# DelSolClock.net
KiCad netlist of a schematic drawn in Altium Designer
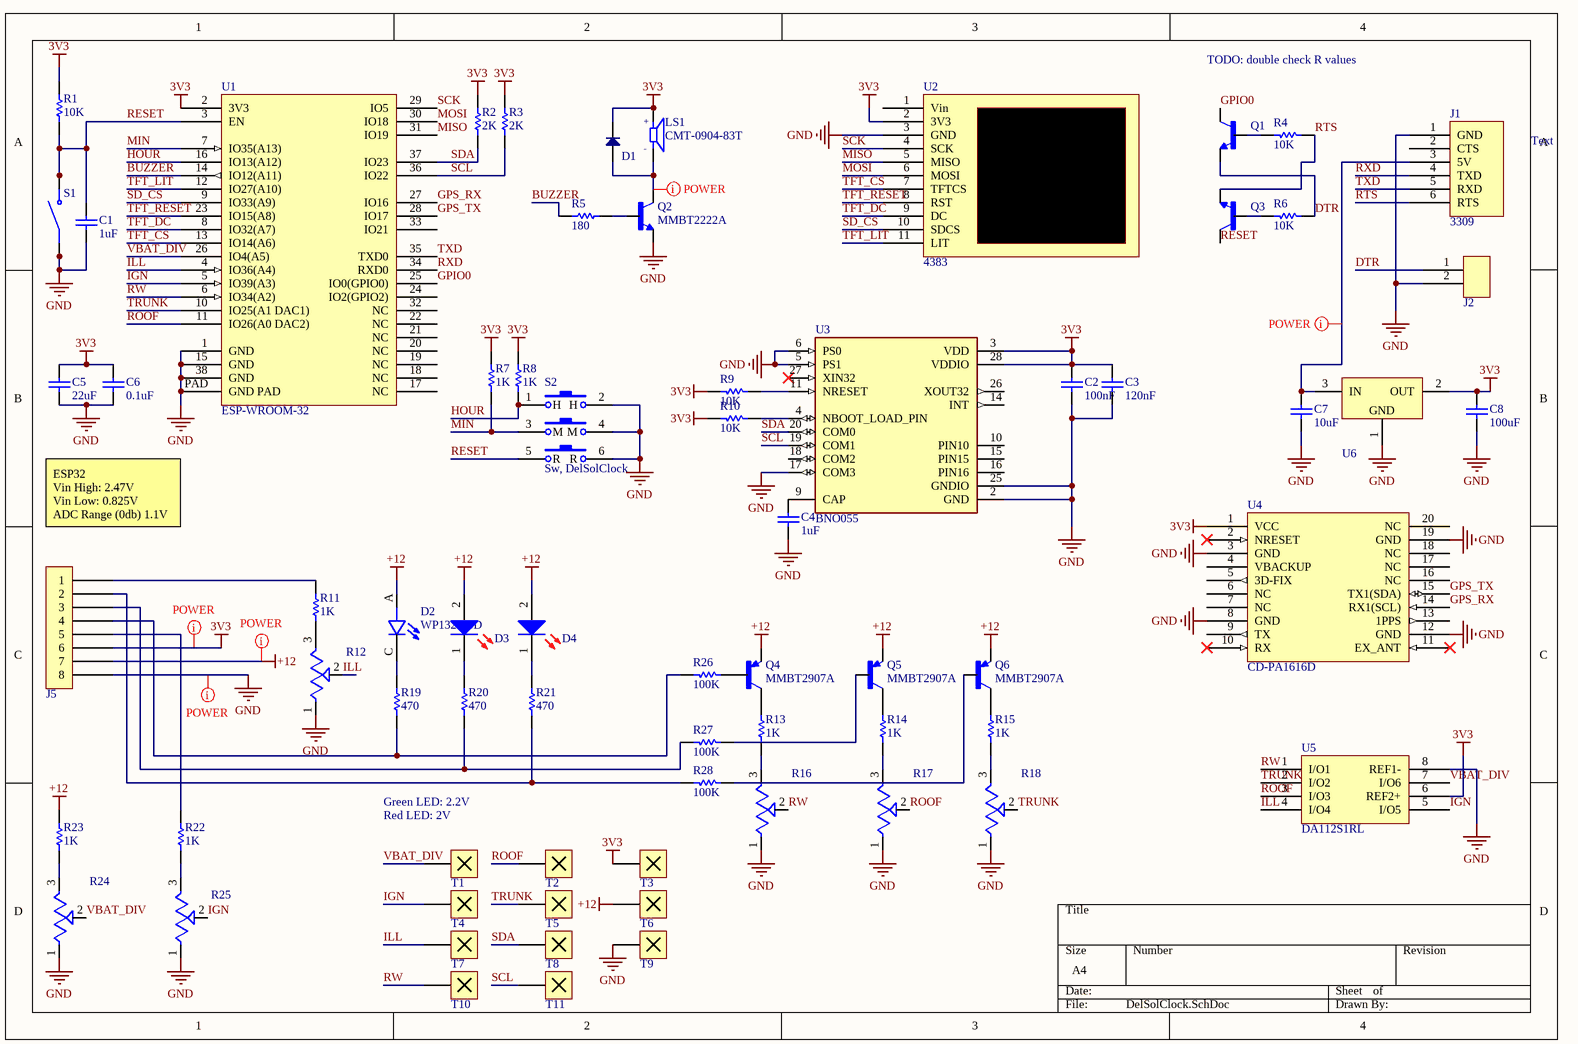
[diagram p0: DelSolClock.SchDoc]

(export (version "E")
  (design (tool "Eeschema 10.0.6"))
  (components
    (comp (ref "C1")
      (value "1uF")
      (footprint "0805 HD - Long")
      (description "Capacitor")
      (fields (field (name "Comment") "CL21B105KOFNNNG"))
      (libsource (lib "DiscreteComponents") (part "Cap"))
    )
    (comp (ref "C2")
      (value "100nF")
      (footprint "0805 HD - Long")
      (description "Capacitor")
      (fields (field (name "Comment") "CL21B104KBCNFNC"))
      (libsource (lib "DiscreteComponents") (part "Cap"))
    )
    (comp (ref "C3")
      (value "120nF")
      (footprint "0805 HD - Long")
      (description "Capacitor")
      (fields (field (name "Comment") "CC0805KRX7R9BB124"))
      (libsource (lib "DiscreteComponents") (part "Cap"))
    )
    (comp (ref "C4")
      (value "1uF")
      (footprint "0805 HD - Long")
      (description "Capacitor")
      (fields (field (name "Comment") "CL21B105KOFNNNG"))
      (libsource (lib "DiscreteComponents") (part "Cap"))
    )
    (comp (ref "C5")
      (value "22uF")
      (footprint "0805 HD - Long")
      (description "Capacitor")
      (fields (field (name "Comment") "Cap"))
      (libsource (lib "DiscreteComponents") (part "Cap"))
    )
    (comp (ref "C6")
      (value "0.1uF")
      (footprint "0805 HD - Long")
      (description "Capacitor")
      (fields (field (name "Comment") "Cap"))
      (libsource (lib "DiscreteComponents") (part "Cap"))
    )
    (comp (ref "C7")
      (value "10uF")
      (footprint "0805 HD - Long")
      (description "Capacitor")
      (fields (field (name "Comment") "Cap"))
      (libsource (lib "DiscreteComponents") (part "Cap"))
    )
    (comp (ref "C8")
      (value "100uF")
      (footprint "0805 HD - Long")
      (description "Capacitor")
      (fields (field (name "Comment") "Cap"))
      (libsource (lib "DiscreteComponents") (part "Cap"))
    )
    (comp (ref "D1")
      (value "SD0805S020S1R0")
      (footprint "0805 HD - Polarized")
      (description "Diode")
      (fields (field (name "MFG") "Panasonic - ECG"))
      (libsource (lib "DiscreteComponents") (part "Diode"))
    )
    (comp (ref "D2")
      (value "WP132XGD")
      (footprint "LEDRD254W50D405H1055")
      (description "Green 568nm LED Indication - Discrete 2.2V Radial")
      (fields (field (name "MF") "{'manufacturer': u'Kingbright'}"))
      (libsource (lib "SnapEDA_Library") (part "WP132XGD"))
    )
    (comp (ref "D3")
      (value "SSL-LX4673ID-LA20")
      (footprint "LED, SSL-LX4673ID-LA20")
      (description "LED, Red, 20mA, through hole, rectangular, 2V")
      (fields (field (name "MFG") "Lumex Opto/Components Inc."))
      (libsource (lib "DiscreteComponents") (part "LED, SSL-LX4673ID-LA20"))
    )
    (comp (ref "D4")
      (value "SSL-LX4673ID-LA20")
      (footprint "LED, SSL-LX4673ID-LA20")
      (description "LED, Red, 20mA, through hole, rectangular, 2V")
      (fields (field (name "MFG") "Lumex Opto/Components Inc."))
      (libsource (lib "DiscreteComponents") (part "LED, SSL-LX4673ID-LA20"))
    )
    (comp (ref "J1")
      (value "3309")
      (footprint "Conn, 3309")
      (description "Conn, Serial USB Adafruit CP2104 Friend")
      (fields (field (name "MFG") "Adafruit"))
      (libsource (lib "Connectors") (part "Conn, 3309"))
    )
    (comp (ref "J2")
      (value "90120-0122")
      (footprint "CONN, HEADER, 2x1 0.1 Pitch Unshrouded")
      (description "Header, 2x1 0.1\" Unshrouded Tin")
      (fields (field (name "MFG") "Molex Connector Corporation"))
      (libsource (lib "Connectors") (part "Conn, 90120-0122"))
    )
    (comp (ref "J5")
      (value "68000-408HLF")
      (footprint "Conn, Header, 8x1 0.1 Pitch Unshrouded")
      (description "Header, 8x1 0.1\" Unshrouded Tin")
      (fields (field (name "MFG") "FCI"))
      (libsource (lib "Connectors") (part "Conn, 68000-408HLF"))
    )
    (comp (ref "LS1")
      (value "CMT-0904-83T")
      (footprint "XDCR_CMT-0904-83T")
      (fields (field (name "MF") "{'manufacturer': u'CUI Devices'}"))
      (libsource (lib "SnapEDA_Library") (part "CMT-0904-83T"))
    )
    (comp (ref "Q1")
      (value "MMBT2222A")
      (footprint "SOT23")
      (description "<h3>2N2222 General Purpose NPN Transistor</h3>")
      (fields (field (name "MF") "{'manufacturer': u'ON Semiconductor'}"))
      (libsource (lib "SnapEDA_Library") (part "MMBT2222A"))
    )
    (comp (ref "Q2")
      (value "MMBT2222A")
      (footprint "SOT23")
      (description "<h3>2N2222 General Purpose NPN Transistor</h3>")
      (fields (field (name "MF") "{'manufacturer': u'ON Semiconductor'}"))
      (libsource (lib "") (part "MMBT2222A_2"))
    )
    (comp (ref "Q3")
      (value "MMBT2222A")
      (footprint "SOT23")
      (description "<h3>2N2222 General Purpose NPN Transistor</h3>")
      (fields (field (name "MF") "{'manufacturer': u'ON Semiconductor'}"))
      (libsource (lib "") (part "MMBT2222A_1"))
    )
    (comp (ref "Q4")
      (value "MMBT2907A")
      (footprint "TRANS_MMBT2907A")
      (description "350mW, PNP Small Signal Transistor")
      (fields (field (name "MF") "{'manufacturer': u'STMicroelectronics'}"))
      (libsource (lib "SnapEDA_Library") (part "MMBT2907A"))
    )
    (comp (ref "Q5")
      (value "MMBT2907A")
      (footprint "TRANS_MMBT2907A")
      (description "350mW, PNP Small Signal Transistor")
      (fields (field (name "MF") "{'manufacturer': u'STMicroelectronics'}"))
      (libsource (lib "SnapEDA_Library") (part "MMBT2907A"))
    )
    (comp (ref "Q6")
      (value "MMBT2907A")
      (footprint "TRANS_MMBT2907A")
      (description "350mW, PNP Small Signal Transistor")
      (fields (field (name "MF") "{'manufacturer': u'STMicroelectronics'}"))
      (libsource (lib "SnapEDA_Library") (part "MMBT2907A"))
    )
    (comp (ref "R1")
      (value "10K")
      (footprint "0805 HD - Long")
      (description "Resistor")
      (fields (field (name "Comment") "RNCP0805FTD10K0"))
      (libsource (lib "DiscreteComponents") (part "Res"))
    )
    (comp (ref "R2")
      (value "2K")
      (footprint "0805 HD - Long")
      (description "Resistor")
      (fields (field (name "Comment") "AC0805FR-7W2KL"))
      (libsource (lib "DiscreteComponents") (part "Res"))
    )
    (comp (ref "R3")
      (value "2K")
      (footprint "0805 HD - Long")
      (description "Resistor")
      (fields (field (name "Comment") "AC0805FR-7W2KL"))
      (libsource (lib "DiscreteComponents") (part "Res"))
    )
    (comp (ref "R4")
      (value "10K")
      (footprint "0805 HD - Long")
      (description "Resistor")
      (fields (field (name "Comment") "RNCP0805FTD10K0"))
      (libsource (lib "DiscreteComponents") (part "Res"))
    )
    (comp (ref "R5")
      (value "180")
      (footprint "0805 HD - Long")
      (description "Resistor")
      (fields (field (name "Comment") "ESR10EZPJ181"))
      (libsource (lib "DiscreteComponents") (part "Res"))
    )
    (comp (ref "R6")
      (value "10K")
      (footprint "0805 HD - Long")
      (description "Resistor")
      (fields (field (name "Comment") "RNCP0805FTD10K0"))
      (libsource (lib "DiscreteComponents") (part "Res"))
    )
    (comp (ref "R7")
      (value "1K")
      (footprint "0805 HD - Long")
      (description "Resistor")
      (fields (field (name "Comment") "CRGH0805J1K0"))
      (libsource (lib "DiscreteComponents") (part "Res"))
    )
    (comp (ref "R8")
      (value "1K")
      (footprint "0805 HD - Long")
      (description "Resistor")
      (fields (field (name "Comment") "CRGH0805J1K0"))
      (libsource (lib "DiscreteComponents") (part "Res"))
    )
    (comp (ref "R9")
      (value "10K")
      (footprint "0805 HD - Long")
      (description "Resistor")
      (fields (field (name "Comment") "RNCP0805FTD10K0"))
      (libsource (lib "DiscreteComponents") (part "Res"))
    )
    (comp (ref "R10")
      (value "10K")
      (footprint "0805 HD - Long")
      (description "Resistor")
      (fields (field (name "Comment") "RNCP0805FTD10K0"))
      (libsource (lib "DiscreteComponents") (part "Res"))
    )
    (comp (ref "R11")
      (value "1K")
      (footprint "0805 HD - Long")
      (description "Resistor")
      (fields (field (name "Comment") "CRGH0805J1K0"))
      (libsource (lib "DiscreteComponents") (part "Res"))
    )
    (comp (ref "R12")
      (value "PVG3G104C01R00")
      (footprint "TRIM_PVG3G104C01R00")
      (description "100 kOhms 0.25W, 1/4W Gull Wing Surface Mount Trimmer Potentiometer Cermet 1 Turn Top Adjustment")
      (fields (field (name "MF") "{'manufacturer': u'Bourns'}"))
      (libsource (lib "SnapEDA_Library") (part "PVG3G104C01R00"))
    )
    (comp (ref "R13")
      (value "1K")
      (footprint "0805 HD - Long")
      (description "Resistor")
      (fields (field (name "Comment") "CRGH0805J1K0"))
      (libsource (lib "DiscreteComponents") (part "Res"))
    )
    (comp (ref "R14")
      (value "1K")
      (footprint "0805 HD - Long")
      (description "Resistor")
      (fields (field (name "Comment") "CRGH0805J1K0"))
      (libsource (lib "DiscreteComponents") (part "Res"))
    )
    (comp (ref "R15")
      (value "1K")
      (footprint "0805 HD - Long")
      (description "Resistor")
      (fields (field (name "Comment") "CRGH0805J1K0"))
      (libsource (lib "DiscreteComponents") (part "Res"))
    )
    (comp (ref "R16")
      (value "PVG3G104C01R00")
      (footprint "TRIM_PVG3G104C01R00")
      (description "10 kOhms 0.25W, 1/4W Gull Wing Surface Mount Trimmer Potentiometer Cermet 1 Turn Top Adjustment")
      (fields (field (name "MF") "{'manufacturer': u'Bourns'}"))
      (libsource (lib "SnapEDA_Library") (part "PVG3G104C01R00"))
    )
    (comp (ref "R17")
      (value "PVG3G104C01R00")
      (footprint "TRIM_PVG3G104C01R00")
      (description "10 kOhms 0.25W, 1/4W Gull Wing Surface Mount Trimmer Potentiometer Cermet 1 Turn Top Adjustment")
      (fields (field (name "MF") "{'manufacturer': u'Bourns'}"))
      (libsource (lib "SnapEDA_Library") (part "PVG3G104C01R00"))
    )
    (comp (ref "R18")
      (value "PVG3G104C01R00")
      (footprint "TRIM_PVG3G104C01R00")
      (description "10 kOhms 0.25W, 1/4W Gull Wing Surface Mount Trimmer Potentiometer Cermet 1 Turn Top Adjustment")
      (fields (field (name "MF") "{'manufacturer': u'Bourns'}"))
      (libsource (lib "SnapEDA_Library") (part "PVG3G104C01R00"))
    )
    (comp (ref "R19")
      (value "470")
      (footprint "0805 HD - Long")
      (description "Resistor")
      (fields (field (name "Comment") "ESR10EZPJ471"))
      (libsource (lib "DiscreteComponents") (part "Res"))
    )
    (comp (ref "R20")
      (value "470")
      (footprint "0805 HD - Long")
      (description "Resistor")
      (fields (field (name "Comment") "ESR10EZPJ471"))
      (libsource (lib "DiscreteComponents") (part "Res"))
    )
    (comp (ref "R21")
      (value "470")
      (footprint "0805 HD - Long")
      (description "Resistor")
      (fields (field (name "Comment") "ESR10EZPJ471"))
      (libsource (lib "DiscreteComponents") (part "Res"))
    )
    (comp (ref "R22")
      (value "1K")
      (footprint "0805 HD - Long")
      (description "Resistor")
      (fields (field (name "Comment") "CRGH0805J1K0"))
      (libsource (lib "DiscreteComponents") (part "Res"))
    )
    (comp (ref "R23")
      (value "1K")
      (footprint "0805 HD - Long")
      (description "Resistor")
      (fields (field (name "Comment") "CRGH0805J1K0"))
      (libsource (lib "DiscreteComponents") (part "Res"))
    )
    (comp (ref "R24")
      (value "PVG3G104C01R00")
      (footprint "TRIM_PVG3G104C01R00")
      (description "100 kOhms 0.25W, 1/4W Gull Wing Surface Mount Trimmer Potentiometer Cermet 1 Turn Top Adjustment")
      (fields (field (name "MF") "{'manufacturer': u'Bourns'}"))
      (libsource (lib "SnapEDA_Library") (part "PVG3G104C01R00"))
    )
    (comp (ref "R25")
      (value "PVG3G104C01R00")
      (footprint "TRIM_PVG3G104C01R00")
      (description "100 kOhms 0.25W, 1/4W Gull Wing Surface Mount Trimmer Potentiometer Cermet 1 Turn Top Adjustment")
      (fields (field (name "MF") "{'manufacturer': u'Bourns'}"))
      (libsource (lib "SnapEDA_Library") (part "PVG3G104C01R00"))
    )
    (comp (ref "R26")
      (value "100K")
      (footprint "0805 HD - Long")
      (description "Resistor")
      (fields (field (name "Comment") "CRGH0805J100K"))
      (libsource (lib "DiscreteComponents") (part "Res"))
    )
    (comp (ref "R27")
      (value "100K")
      (footprint "0805 HD - Long")
      (description "Resistor")
      (fields (field (name "Comment") "CRGH0805J100K"))
      (libsource (lib "DiscreteComponents") (part "Res"))
    )
    (comp (ref "R28")
      (value "100K")
      (footprint "0805 HD - Long")
      (description "Resistor")
      (fields (field (name "Comment") "CRGH0805J100K"))
      (libsource (lib "DiscreteComponents") (part "Res"))
    )
    (comp (ref "S1")
      (value "8-1437565-0")
      (footprint "SW_8-1437565-0")
      (fields (field (name "MF") "{'manufacturer': u'TE Connectivity'}"))
      (libsource (lib "SnapEDA_Library") (part "8-1437565-0"))
    )
    (comp (ref "S2")
      (value "Sw, DelSolClock")
      (footprint "Sw, DelSolClock")
      (description "Switch, Del Sol Clock, elastomeric")
      (libsource (lib "Connectors") (part "Sw, DelSolClock"))
    )
    (comp (ref "T1")
      (value "Test Point")
      (footprint "5002 Test Point")
      (fields (field (name "MFG") "Keystone Electronics"))
      (libsource (lib "Connectors") (part "Test Point"))
    )
    (comp (ref "T2")
      (value "Test Point")
      (footprint "5002 Test Point")
      (fields (field (name "MFG") "Keystone Electronics"))
      (libsource (lib "Connectors") (part "Test Point"))
    )
    (comp (ref "T3")
      (value "Test Point")
      (footprint "5002 Test Point")
      (fields (field (name "MFG") "Keystone Electronics"))
      (libsource (lib "Connectors") (part "Test Point"))
    )
    (comp (ref "T4")
      (value "Test Point")
      (footprint "5002 Test Point")
      (fields (field (name "MFG") "Keystone Electronics"))
      (libsource (lib "Connectors") (part "Test Point"))
    )
    (comp (ref "T5")
      (value "Test Point")
      (footprint "5002 Test Point")
      (fields (field (name "MFG") "Keystone Electronics"))
      (libsource (lib "Connectors") (part "Test Point"))
    )
    (comp (ref "T6")
      (value "Test Point")
      (footprint "5002 Test Point")
      (fields (field (name "MFG") "Keystone Electronics"))
      (libsource (lib "Connectors") (part "Test Point"))
    )
    (comp (ref "T7")
      (value "Test Point")
      (footprint "5002 Test Point")
      (fields (field (name "MFG") "Keystone Electronics"))
      (libsource (lib "Connectors") (part "Test Point"))
    )
    (comp (ref "T8")
      (value "Test Point")
      (footprint "5002 Test Point")
      (fields (field (name "MFG") "Keystone Electronics"))
      (libsource (lib "Connectors") (part "Test Point"))
    )
    (comp (ref "T9")
      (value "Test Point")
      (footprint "5002 Test Point")
      (fields (field (name "MFG") "Keystone Electronics"))
      (libsource (lib "Connectors") (part "Test Point"))
    )
    (comp (ref "T10")
      (value "Test Point")
      (footprint "5002 Test Point")
      (fields (field (name "MFG") "Keystone Electronics"))
      (libsource (lib "Connectors") (part "Test Point"))
    )
    (comp (ref "T11")
      (value "Test Point")
      (footprint "5002 Test Point")
      (fields (field (name "MFG") "Keystone Electronics"))
      (libsource (lib "Connectors") (part "Test Point"))
    )
    (comp (ref "U1")
      (value "ESP-WROOM-32")
      (footprint "MODULE, ESP32-WROOM-32")
      (description "Module, Wifi Module, ESP32 4MB Flash 520K RAM")
      (fields (field (name "MFG") "Espressif"))
      (libsource (lib "Modules") (part "Module, ESP-WROOM-32"))
    )
    (comp (ref "U2")
      (value "4383")
      (footprint "Module, Adafruit TFT")
      (description "Module, Display, Graphic TFT 240x135 Color, ST7789")
      (fields (field (name "MFG") "Adafruit"))
      (libsource (lib "Modules") (part "Module, Adafruit TFT"))
    )
    (comp (ref "U3")
      (value "BNO055")
      (footprint "LGA28R50P4X10_380X520X100")
      (description "BNO055 9-axis Absolute Orientation Sensor ( SiP ) w/Sensors and Sensor Fusion")
      (fields (field (name "MF") "{'manufacturer': u'Bosch'}"))
      (libsource (lib "SnapEDA_Library") (part "BNO055"))
    )
    (comp (ref "U4")
      (value "CD-PA1616D")
      (footprint "Module, CD-PA1616D")
      (description "Module, GPS, module with integrated antenna")
      (fields (field (name "MFG") "CD Technology"))
      (libsource (lib "Modules") (part "Module, CD-PA1616D"))
    )
    (comp (ref "U5")
      (value "DA112S1RL")
      (footprint "IC, DA112S1RL")
      (description "IC, TVS Diode, 6 channel")
      (libsource (lib "IntegratedCircuits") (part "IC, DA112S1RL"))
    )
    (comp (ref "U6")
      (value "TLV1117-33CDCYR")
      (footprint "SOT230P700X180-4N Regulator 3.3V 800mA")
      (description "IC, Regulator 3.3V 800mA LDO 15V max SOT-223")
      (fields (field (name "MFG") "Texas Instruments"))
      (libsource (lib "IntegratedCircuits") (part "IC, TLV1117-33CDCYR"))
    )
  )
  (nets
    (net (code "1") (name "+12") (class "Default")
      (node (ref "D2") (pin "A") (pinfunction "A_A") (pintype "passive"))
      (node (ref "D3") (pin "2") (pinfunction "A_2") (pintype "passive"))
      (node (ref "D4") (pin "2") (pinfunction "A_2") (pintype "passive"))
      (node (ref "J5") (pin "7") (pinfunction "7_7") (pintype "passive"))
      (node (ref "Q4") (pin "2") (pinfunction "E_2") (pintype "passive"))
      (node (ref "Q5") (pin "2") (pinfunction "E_2") (pintype "passive"))
      (node (ref "Q6") (pin "2") (pinfunction "E_2") (pintype "passive"))
      (node (ref "R23") (pin "1") (pinfunction "1_1") (pintype "passive"))
      (node (ref "T6") (pin "1") (pinfunction "1_1") (pintype "passive"))
    )
    (net (code "2") (name "/BUZZER") (class "Default")
      (node (ref "R5") (pin "1") (pinfunction "1_1") (pintype "passive"))
      (node (ref "U1") (pin "14") (pinfunction "IO12(A11)_14") (pintype "output"))
    )
    (net (code "3") (name "/DTR") (class "Default")
      (node (ref "J2") (pin "1") (pintype "passive"))
      (node (ref "Q1") (pin "2") (pinfunction "E_2") (pintype "passive"))
      (node (ref "R6") (pin "2") (pinfunction "2_2") (pintype "passive"))
    )
    (net (code "4") (name "/GPIO0") (class "Default")
      (node (ref "Q1") (pin "3") (pinfunction "C_3") (pintype "passive"))
      (node (ref "U1") (pin "25") (pinfunction "IO0(GPIO0)_25") (pintype "passive"))
    )
    (net (code "5") (name "/GPS_RX") (class "Default")
      (node (ref "U1") (pin "27") (pinfunction "IO16_27") (pintype "passive"))
      (node (ref "U4") (pin "14") (pinfunction "RX1(SCL)_14") (pintype "input"))
    )
    (net (code "6") (name "/GPS_TX") (class "Default")
      (node (ref "U1") (pin "28") (pinfunction "IO17_28") (pintype "passive"))
      (node (ref "U4") (pin "15") (pinfunction "TX1(SDA)_15") (pintype "bidirectional"))
    )
    (net (code "7") (name "/HOUR") (class "Default")
      (node (ref "R8") (pin "1") (pinfunction "1_1") (pintype "passive"))
      (node (ref "S2") (pin "1") (pinfunction "H_1") (pintype "passive"))
      (node (ref "U1") (pin "16") (pinfunction "IO13(A12)_16") (pintype "passive"))
    )
    (net (code "8") (name "/IGN") (class "Default")
      (node (ref "R25") (pin "2") (pinfunction "WIPER_2") (pintype "passive"))
      (node (ref "T4") (pin "1") (pinfunction "1_1") (pintype "passive"))
      (node (ref "U1") (pin "5") (pinfunction "IO39(A3)_5") (pintype "input"))
      (node (ref "U5") (pin "5") (pinfunction "I/O5_5") (pintype "passive"))
    )
    (net (code "9") (name "/ILL") (class "Default")
      (node (ref "R12") (pin "2") (pinfunction "WIPER_2") (pintype "passive"))
      (node (ref "T7") (pin "1") (pinfunction "1_1") (pintype "passive"))
      (node (ref "U1") (pin "4") (pinfunction "IO36(A4)_4") (pintype "input"))
      (node (ref "U5") (pin "4") (pinfunction "I/O4_4") (pintype "passive"))
    )
    (net (code "10") (name "/MIN") (class "Default")
      (node (ref "R7") (pin "1") (pinfunction "1_1") (pintype "passive"))
      (node (ref "S2") (pin "3") (pinfunction "M_3") (pintype "passive"))
      (node (ref "U1") (pin "7") (pinfunction "IO35(A13)_7") (pintype "input"))
    )
    (net (code "11") (name "/MISO") (class "Default")
      (node (ref "U1") (pin "31") (pinfunction "IO19_31") (pintype "passive"))
      (node (ref "U2") (pin "5") (pinfunction "MISO_5") (pintype "passive"))
    )
    (net (code "12") (name "/MOSI") (class "Default")
      (node (ref "U1") (pin "30") (pinfunction "IO18_30") (pintype "passive"))
      (node (ref "U2") (pin "6") (pinfunction "MOSI_6") (pintype "passive"))
    )
    (net (code "13") (name "/RESET") (class "Default")
      (node (ref "C1") (pin "2") (pinfunction "2_2") (pintype "passive"))
      (node (ref "Q3") (pin "3") (pinfunction "C_3") (pintype "passive"))
      (node (ref "R1") (pin "1") (pinfunction "1_1") (pintype "passive"))
      (node (ref "S1") (pin "3") (pinfunction "NO_3") (pintype "passive"))
      (node (ref "S1") (pin "4") (pinfunction "NO_4") (pintype "passive"))
      (node (ref "S2") (pin "5") (pinfunction "R_5") (pintype "passive"))
      (node (ref "U1") (pin "3") (pinfunction "EN_3") (pintype "passive"))
    )
    (net (code "14") (name "/ROOF") (class "Default")
      (node (ref "R17") (pin "2") (pinfunction "WIPER_2") (pintype "passive"))
      (node (ref "T2") (pin "1") (pinfunction "1_1") (pintype "passive"))
      (node (ref "U1") (pin "11") (pinfunction "IO26(A0_DAC2)_11") (pintype "passive"))
      (node (ref "U5") (pin "3") (pinfunction "I/O3_3") (pintype "passive"))
    )
    (net (code "15") (name "/RTS") (class "Default")
      (node (ref "J1") (pin "6") (pinfunction "RTS_6") (pintype "passive"))
      (node (ref "Q3") (pin "2") (pinfunction "E_2") (pintype "passive"))
      (node (ref "R4") (pin "2") (pinfunction "2_2") (pintype "passive"))
    )
    (net (code "16") (name "/RW") (class "Default")
      (node (ref "R16") (pin "2") (pinfunction "WIPER_2") (pintype "passive"))
      (node (ref "T10") (pin "1") (pinfunction "1_1") (pintype "passive"))
      (node (ref "U1") (pin "6") (pinfunction "IO34(A2)_6") (pintype "input"))
      (node (ref "U5") (pin "1") (pinfunction "I/O1_1") (pintype "passive"))
    )
    (net (code "17") (name "/RXD") (class "Default")
      (node (ref "J1") (pin "4") (pinfunction "TXD_4") (pintype "passive"))
      (node (ref "U1") (pin "34") (pinfunction "RXD0_34") (pintype "passive"))
    )
    (net (code "18") (name "/SCK") (class "Default")
      (node (ref "U1") (pin "29") (pinfunction "IO5_29") (pintype "passive"))
      (node (ref "U2") (pin "4") (pinfunction "SCK_4") (pintype "passive"))
    )
    (net (code "19") (name "/SCL") (class "Default")
      (node (ref "R3") (pin "1") (pinfunction "1_1") (pintype "passive"))
      (node (ref "T11") (pin "1") (pinfunction "1_1") (pintype "passive"))
      (node (ref "U1") (pin "36") (pinfunction "IO22_36") (pintype "passive"))
      (node (ref "U3") (pin "19") (pinfunction "COM1_19") (pintype "bidirectional"))
    )
    (net (code "20") (name "/SDA") (class "Default")
      (node (ref "R2") (pin "1") (pinfunction "1_1") (pintype "passive"))
      (node (ref "T8") (pin "1") (pinfunction "1_1") (pintype "passive"))
      (node (ref "U1") (pin "37") (pinfunction "IO23_37") (pintype "passive"))
      (node (ref "U3") (pin "20") (pinfunction "COM0_20") (pintype "bidirectional"))
    )
    (net (code "21") (name "/SD_CS") (class "Default")
      (node (ref "U1") (pin "9") (pinfunction "IO33(A9)_9") (pintype "passive"))
      (node (ref "U2") (pin "10") (pinfunction "SDCS_10") (pintype "passive"))
    )
    (net (code "22") (name "/TFT_CS") (class "Default")
      (node (ref "U1") (pin "13") (pinfunction "IO14(A6)_13") (pintype "passive"))
      (node (ref "U2") (pin "7") (pinfunction "TFTCS_7") (pintype "passive"))
    )
    (net (code "23") (name "/TFT_DC") (class "Default")
      (node (ref "U1") (pin "8") (pinfunction "IO32(A7)_8") (pintype "passive"))
      (node (ref "U2") (pin "9") (pinfunction "DC_9") (pintype "passive"))
    )
    (net (code "24") (name "/TFT_LIT") (class "Default")
      (node (ref "U1") (pin "12") (pinfunction "IO27(A10)_12") (pintype "passive"))
      (node (ref "U2") (pin "11") (pinfunction "LIT_11") (pintype "passive"))
    )
    (net (code "25") (name "/TFT_RESET") (class "Default")
      (node (ref "U1") (pin "23") (pinfunction "IO15(A8)_23") (pintype "passive"))
      (node (ref "U2") (pin "8") (pinfunction "RST_8") (pintype "passive"))
    )
    (net (code "26") (name "/TRUNK") (class "Default")
      (node (ref "R18") (pin "2") (pinfunction "WIPER_2") (pintype "passive"))
      (node (ref "T5") (pin "1") (pinfunction "1_1") (pintype "passive"))
      (node (ref "U1") (pin "10") (pinfunction "IO25(A1_DAC1)_10") (pintype "passive"))
      (node (ref "U5") (pin "2") (pinfunction "I/O2_2") (pintype "passive"))
    )
    (net (code "27") (name "/TXD") (class "Default")
      (node (ref "J1") (pin "5") (pinfunction "RXD_5") (pintype "passive"))
      (node (ref "U1") (pin "35") (pinfunction "TXD0_35") (pintype "passive"))
    )
    (net (code "28") (name "/VBAT_DIV") (class "Default")
      (node (ref "R24") (pin "2") (pinfunction "WIPER_2") (pintype "passive"))
      (node (ref "T1") (pin "1") (pinfunction "1_1") (pintype "passive"))
      (node (ref "U1") (pin "26") (pinfunction "IO4(A5)_26") (pintype "passive"))
      (node (ref "U5") (pin "7") (pinfunction "I/O6_7") (pintype "passive"))
    )
    (net (code "29") (name "3V3") (class "Default")
      (node (ref "C2") (pin "1") (pinfunction "1_1") (pintype "passive"))
      (node (ref "C3") (pin "1") (pinfunction "1_1") (pintype "passive"))
      (node (ref "C5") (pin "2") (pinfunction "2_2") (pintype "passive"))
      (node (ref "C6") (pin "2") (pinfunction "2_2") (pintype "passive"))
      (node (ref "C8") (pin "2") (pinfunction "2_2") (pintype "passive"))
      (node (ref "D1") (pin "1") (pinfunction "C_1") (pintype "passive"))
      (node (ref "J5") (pin "6") (pinfunction "6_6") (pintype "passive"))
      (node (ref "LS1") (pin "P") (pinfunction "P_P") (pintype "passive"))
      (node (ref "R1") (pin "2") (pinfunction "2_2") (pintype "passive"))
      (node (ref "R10") (pin "1") (pinfunction "1_1") (pintype "passive"))
      (node (ref "R2") (pin "2") (pinfunction "2_2") (pintype "passive"))
      (node (ref "R3") (pin "2") (pinfunction "2_2") (pintype "passive"))
      (node (ref "R7") (pin "2") (pinfunction "2_2") (pintype "passive"))
      (node (ref "R8") (pin "2") (pinfunction "2_2") (pintype "passive"))
      (node (ref "R9") (pin "1") (pinfunction "1_1") (pintype "passive"))
      (node (ref "T3") (pin "1") (pinfunction "1_1") (pintype "passive"))
      (node (ref "U1") (pin "2") (pinfunction "3V3_2") (pintype "passive"))
      (node (ref "U2") (pin "2") (pinfunction "3V3_2") (pintype "passive"))
      (node (ref "U3") (pin "28") (pinfunction "VDDIO_28") (pintype "power_in"))
      (node (ref "U3") (pin "3") (pinfunction "VDD_3") (pintype "power_in"))
      (node (ref "U4") (pin "1") (pinfunction "VCC_1") (pintype "power_in"))
      (node (ref "U5") (pin "6") (pinfunction "REF2+_6") (pintype "passive"))
      (node (ref "U6") (pin "2") (pinfunction "OUT_2") (pintype "passive"))
    )
    (net (code "30") (name "GND") (class "Default")
      (node (ref "C1") (pin "1") (pinfunction "1_1") (pintype "passive"))
      (node (ref "C2") (pin "2") (pinfunction "2_2") (pintype "passive"))
      (node (ref "C3") (pin "2") (pinfunction "2_2") (pintype "passive"))
      (node (ref "C4") (pin "1") (pinfunction "1_1") (pintype "passive"))
      (node (ref "C5") (pin "1") (pinfunction "1_1") (pintype "passive"))
      (node (ref "C6") (pin "1") (pinfunction "1_1") (pintype "passive"))
      (node (ref "C7") (pin "1") (pinfunction "1_1") (pintype "passive"))
      (node (ref "C8") (pin "1") (pinfunction "1_1") (pintype "passive"))
      (node (ref "J1") (pin "1") (pinfunction "GND_1") (pintype "passive"))
      (node (ref "J2") (pin "2") (pintype "passive"))
      (node (ref "J5") (pin "8") (pinfunction "8_8") (pintype "passive"))
      (node (ref "Q2") (pin "2") (pinfunction "E_2") (pintype "passive"))
      (node (ref "R12") (pin "1") (pinfunction "CCW_1") (pintype "passive"))
      (node (ref "R16") (pin "1") (pinfunction "CCW_1") (pintype "passive"))
      (node (ref "R17") (pin "1") (pinfunction "CCW_1") (pintype "passive"))
      (node (ref "R18") (pin "1") (pinfunction "CCW_1") (pintype "passive"))
      (node (ref "R24") (pin "1") (pinfunction "CCW_1") (pintype "passive"))
      (node (ref "R25") (pin "1") (pinfunction "CCW_1") (pintype "passive"))
      (node (ref "S1") (pin "1") (pinfunction "COM_1") (pintype "passive"))
      (node (ref "S1") (pin "2") (pinfunction "COM_2") (pintype "passive"))
      (node (ref "S2") (pin "2") (pinfunction "H_2") (pintype "passive"))
      (node (ref "S2") (pin "4") (pinfunction "M_4") (pintype "passive"))
      (node (ref "S2") (pin "6") (pinfunction "R_6") (pintype "passive"))
      (node (ref "T9") (pin "1") (pinfunction "1_1") (pintype "passive"))
      (node (ref "U1") (pin "1") (pinfunction "GND_1") (pintype "passive"))
      (node (ref "U1") (pin "15") (pinfunction "GND_15") (pintype "passive"))
      (node (ref "U1") (pin "38") (pinfunction "GND_38") (pintype "passive"))
      (node (ref "U1") (pin "PAD") (pinfunction "GND_PAD_PAD") (pintype "passive"))
      (node (ref "U2") (pin "3") (pinfunction "GND_3") (pintype "passive"))
      (node (ref "U3") (pin "17") (pinfunction "COM3_17") (pintype "bidirectional"))
      (node (ref "U3") (pin "2") (pinfunction "GND_2") (pintype "power_in"))
      (node (ref "U3") (pin "25") (pinfunction "GNDIO_25") (pintype "power_in"))
      (node (ref "U3") (pin "5") (pinfunction "PS1_5") (pintype "input"))
      (node (ref "U3") (pin "6") (pinfunction "PS0_6") (pintype "input"))
      (node (ref "U4") (pin "12") (pinfunction "GND_12") (pintype "power_in"))
      (node (ref "U4") (pin "19") (pinfunction "GND_19") (pintype "power_in"))
      (node (ref "U4") (pin "3") (pinfunction "GND_3") (pintype "power_in"))
      (node (ref "U4") (pin "8") (pinfunction "GND_8") (pintype "power_in"))
      (node (ref "U5") (pin "8") (pinfunction "REF1-_8") (pintype "passive"))
      (node (ref "U6") (pin "1") (pinfunction "GND_1") (pintype "passive"))
    )
    (net (code "31") (name "Net-(D1-A)") (class "Default")
      (node (ref "D1") (pin "2") (pinfunction "A_2") (pintype "passive"))
      (node (ref "LS1") (pin "N") (pinfunction "N_N") (pintype "passive"))
      (node (ref "Q2") (pin "3") (pinfunction "C_3") (pintype "passive"))
    )
    (net (code "32") (name "Net-(D2-PadC)") (class "Default")
      (node (ref "D2") (pin "C") (pinfunction "C_C") (pintype "passive"))
      (node (ref "R19") (pin "2") (pinfunction "2_2") (pintype "passive"))
    )
    (net (code "33") (name "Net-(D3-K)") (class "Default")
      (node (ref "D3") (pin "1") (pinfunction "K_1") (pintype "passive"))
      (node (ref "R20") (pin "2") (pinfunction "2_2") (pintype "passive"))
    )
    (net (code "34") (name "Net-(D4-K)") (class "Default")
      (node (ref "D4") (pin "1") (pinfunction "K_1") (pintype "passive"))
      (node (ref "R21") (pin "2") (pinfunction "2_2") (pintype "passive"))
    )
    (net (code "35") (name "Net-(J1-5V)") (class "Default")
      (node (ref "C7") (pin "2") (pinfunction "2_2") (pintype "passive"))
      (node (ref "J1") (pin "3") (pinfunction "5V_3") (pintype "passive"))
      (node (ref "U6") (pin "3") (pinfunction "IN_3") (pintype "passive"))
    )
    (net (code "36") (name "Net-(J5-Pad1)") (class "Default")
      (node (ref "J5") (pin "1") (pinfunction "1_1") (pintype "passive"))
      (node (ref "R11") (pin "2") (pinfunction "2_2") (pintype "passive"))
    )
    (net (code "37") (name "Net-(J5-Pad2)") (class "Default")
      (node (ref "J5") (pin "2") (pinfunction "2_2") (pintype "passive"))
      (node (ref "R21") (pin "1") (pinfunction "1_1") (pintype "passive"))
      (node (ref "R28") (pin "1") (pinfunction "1_1") (pintype "passive"))
    )
    (net (code "38") (name "Net-(J5-Pad3)") (class "Default")
      (node (ref "J5") (pin "3") (pinfunction "3_3") (pintype "passive"))
      (node (ref "R20") (pin "1") (pinfunction "1_1") (pintype "passive"))
      (node (ref "R27") (pin "1") (pinfunction "1_1") (pintype "passive"))
    )
    (net (code "39") (name "Net-(J5-Pad4)") (class "Default")
      (node (ref "J5") (pin "4") (pinfunction "4_4") (pintype "passive"))
      (node (ref "R19") (pin "1") (pinfunction "1_1") (pintype "passive"))
      (node (ref "R26") (pin "1") (pinfunction "1_1") (pintype "passive"))
    )
    (net (code "40") (name "Net-(J5-Pad5)") (class "Default")
      (node (ref "J5") (pin "5") (pinfunction "5_5") (pintype "passive"))
      (node (ref "R22") (pin "1") (pinfunction "1_1") (pintype "passive"))
    )
    (net (code "41") (name "Net-(Q1-B)") (class "Default")
      (node (ref "Q1") (pin "1") (pinfunction "B_1") (pintype "passive"))
      (node (ref "R4") (pin "1") (pinfunction "1_1") (pintype "passive"))
    )
    (net (code "42") (name "Net-(Q2-B)") (class "Default")
      (node (ref "Q2") (pin "1") (pinfunction "B_1") (pintype "passive"))
      (node (ref "R5") (pin "2") (pinfunction "2_2") (pintype "passive"))
    )
    (net (code "43") (name "Net-(Q3-B)") (class "Default")
      (node (ref "Q3") (pin "1") (pinfunction "B_1") (pintype "passive"))
      (node (ref "R6") (pin "1") (pinfunction "1_1") (pintype "passive"))
    )
    (net (code "44") (name "Net-(Q4-B)") (class "Default")
      (node (ref "Q4") (pin "1") (pinfunction "B_1") (pintype "passive"))
      (node (ref "R26") (pin "2") (pinfunction "2_2") (pintype "passive"))
    )
    (net (code "45") (name "Net-(Q4-C)") (class "Default")
      (node (ref "Q4") (pin "3") (pinfunction "C_3") (pintype "passive"))
      (node (ref "R13") (pin "2") (pinfunction "2_2") (pintype "passive"))
    )
    (net (code "46") (name "Net-(Q5-B)") (class "Default")
      (node (ref "Q5") (pin "1") (pinfunction "B_1") (pintype "passive"))
      (node (ref "R27") (pin "2") (pinfunction "2_2") (pintype "passive"))
    )
    (net (code "47") (name "Net-(Q5-C)") (class "Default")
      (node (ref "Q5") (pin "3") (pinfunction "C_3") (pintype "passive"))
      (node (ref "R14") (pin "2") (pinfunction "2_2") (pintype "passive"))
    )
    (net (code "48") (name "Net-(Q6-B)") (class "Default")
      (node (ref "Q6") (pin "1") (pinfunction "B_1") (pintype "passive"))
      (node (ref "R28") (pin "2") (pinfunction "2_2") (pintype "passive"))
    )
    (net (code "49") (name "Net-(Q6-C)") (class "Default")
      (node (ref "Q6") (pin "3") (pinfunction "C_3") (pintype "passive"))
      (node (ref "R15") (pin "2") (pinfunction "2_2") (pintype "passive"))
    )
    (net (code "50") (name "Net-(R12-CW)") (class "Default")
      (node (ref "R11") (pin "1") (pinfunction "1_1") (pintype "passive"))
      (node (ref "R12") (pin "3") (pinfunction "CW_3") (pintype "passive"))
    )
    (net (code "51") (name "Net-(R16-CW)") (class "Default")
      (node (ref "R13") (pin "1") (pinfunction "1_1") (pintype "passive"))
      (node (ref "R16") (pin "3") (pinfunction "CW_3") (pintype "passive"))
    )
    (net (code "52") (name "Net-(R17-CW)") (class "Default")
      (node (ref "R14") (pin "1") (pinfunction "1_1") (pintype "passive"))
      (node (ref "R17") (pin "3") (pinfunction "CW_3") (pintype "passive"))
    )
    (net (code "53") (name "Net-(R18-CW)") (class "Default")
      (node (ref "R15") (pin "1") (pinfunction "1_1") (pintype "passive"))
      (node (ref "R18") (pin "3") (pinfunction "CW_3") (pintype "passive"))
    )
    (net (code "54") (name "Net-(R24-CW)") (class "Default")
      (node (ref "R23") (pin "2") (pinfunction "2_2") (pintype "passive"))
      (node (ref "R24") (pin "3") (pinfunction "CW_3") (pintype "passive"))
    )
    (net (code "55") (name "Net-(R25-CW)") (class "Default")
      (node (ref "R22") (pin "2") (pinfunction "2_2") (pintype "passive"))
      (node (ref "R25") (pin "3") (pinfunction "CW_3") (pintype "passive"))
    )
    (net (code "56") (name "Net-(U3-CAP)") (class "Default")
      (node (ref "C4") (pin "2") (pinfunction "2_2") (pintype "passive"))
      (node (ref "U3") (pin "9") (pinfunction "CAP_9") (pintype "passive"))
    )
    (net (code "57") (name "Net-(U3-NBOOT_LOAD_PIN)") (class "Default")
      (node (ref "R10") (pin "2") (pinfunction "2_2") (pintype "passive"))
      (node (ref "U3") (pin "4") (pinfunction "NBOOT_LOAD_PIN_4") (pintype "bidirectional"))
    )
    (net (code "58") (name "Net-(U3-NRESET)") (class "Default")
      (node (ref "R9") (pin "2") (pinfunction "2_2") (pintype "passive"))
      (node (ref "U3") (pin "11") (pinfunction "NRESET_11") (pintype "input"))
    )
    (net (code "59") (name "unconnected-(J1-CTS-Pad2)") (class "Default")
      (node (ref "J1") (pin "2") (pinfunction "CTS_2") (pintype "passive"))
    )
    (net (code "60") (name "unconnected-(U1-IO2(GPIO2)-Pad24)") (class "Default")
      (node (ref "U1") (pin "24") (pinfunction "IO2(GPIO2)_24") (pintype "passive"))
    )
    (net (code "61") (name "unconnected-(U1-IO21-Pad33)") (class "Default")
      (node (ref "U1") (pin "33") (pinfunction "IO21_33") (pintype "passive"))
    )
    (net (code "62") (name "unconnected-(U1-NC-Pad17)") (class "Default")
      (node (ref "U1") (pin "17") (pinfunction "NC_17") (pintype "passive"))
    )
    (net (code "63") (name "unconnected-(U1-NC-Pad18)") (class "Default")
      (node (ref "U1") (pin "18") (pinfunction "NC_18") (pintype "passive"))
    )
    (net (code "64") (name "unconnected-(U1-NC-Pad19)") (class "Default")
      (node (ref "U1") (pin "19") (pinfunction "NC_19") (pintype "passive"))
    )
    (net (code "65") (name "unconnected-(U1-NC-Pad20)") (class "Default")
      (node (ref "U1") (pin "20") (pinfunction "NC_20") (pintype "passive"))
    )
    (net (code "66") (name "unconnected-(U1-NC-Pad21)") (class "Default")
      (node (ref "U1") (pin "21") (pinfunction "NC_21") (pintype "passive"))
    )
    (net (code "67") (name "unconnected-(U1-NC-Pad22)") (class "Default")
      (node (ref "U1") (pin "22") (pinfunction "NC_22") (pintype "passive"))
    )
    (net (code "68") (name "unconnected-(U1-NC-Pad32)") (class "Default")
      (node (ref "U1") (pin "32") (pinfunction "NC_32") (pintype "passive"))
    )
    (net (code "69") (name "unconnected-(U2-Vin-Pad1)") (class "Default")
      (node (ref "U2") (pin "1") (pinfunction "Vin_1") (pintype "passive"))
    )
    (net (code "70") (name "unconnected-(U3-COM2-Pad18)") (class "Default")
      (node (ref "U3") (pin "18") (pinfunction "COM2_18") (pintype "bidirectional"))
    )
    (net (code "71") (name "unconnected-(U3-INT-Pad14)") (class "Default")
      (node (ref "U3") (pin "14") (pinfunction "INT_14") (pintype "output"))
    )
    (net (code "72") (name "unconnected-(U3-PIN10-Pad10)") (class "Default")
      (node (ref "U3") (pin "10") (pinfunction "PIN10_10") (pintype "power_in"))
    )
    (net (code "73") (name "unconnected-(U3-PIN15-Pad15)") (class "Default")
      (node (ref "U3") (pin "15") (pinfunction "PIN15_15") (pintype "power_in"))
    )
    (net (code "74") (name "unconnected-(U3-PIN16-Pad16)") (class "Default")
      (node (ref "U3") (pin "16") (pinfunction "PIN16_16") (pintype "power_in"))
    )
    (net (code "75") (name "unconnected-(U3-XIN32-Pad27)") (class "Default")
      (node (ref "U3") (pin "27") (pinfunction "XIN32_27") (pintype "input+no_connect"))
    )
    (net (code "76") (name "unconnected-(U3-XOUT32-Pad26)") (class "Default")
      (node (ref "U3") (pin "26") (pinfunction "XOUT32_26") (pintype "output"))
    )
    (net (code "77") (name "unconnected-(U4-1PPS-Pad13)") (class "Default")
      (node (ref "U4") (pin "13") (pinfunction "1PPS_13") (pintype "output"))
    )
    (net (code "78") (name "unconnected-(U4-3D-FIX-Pad5)") (class "Default")
      (node (ref "U4") (pin "5") (pinfunction "3D-FIX_5") (pintype "output"))
    )
    (net (code "79") (name "unconnected-(U4-EX_ANT-Pad11)") (class "Default")
      (node (ref "U4") (pin "11") (pinfunction "EX_ANT_11") (pintype "input+no_connect"))
    )
    (net (code "80") (name "unconnected-(U4-NC-Pad6)") (class "Default")
      (node (ref "U4") (pin "6") (pinfunction "NC_6") (pintype "passive"))
    )
    (net (code "81") (name "unconnected-(U4-NC-Pad7)") (class "Default")
      (node (ref "U4") (pin "7") (pinfunction "NC_7") (pintype "passive"))
    )
    (net (code "82") (name "unconnected-(U4-NC-Pad16)") (class "Default")
      (node (ref "U4") (pin "16") (pinfunction "NC_16") (pintype "passive"))
    )
    (net (code "83") (name "unconnected-(U4-NC-Pad17)") (class "Default")
      (node (ref "U4") (pin "17") (pinfunction "NC_17") (pintype "passive"))
    )
    (net (code "84") (name "unconnected-(U4-NC-Pad18)") (class "Default")
      (node (ref "U4") (pin "18") (pinfunction "NC_18") (pintype "passive"))
    )
    (net (code "85") (name "unconnected-(U4-NC-Pad20)") (class "Default")
      (node (ref "U4") (pin "20") (pinfunction "NC_20") (pintype "passive"))
    )
    (net (code "86") (name "unconnected-(U4-NRESET-Pad2)") (class "Default")
      (node (ref "U4") (pin "2") (pinfunction "NRESET_2") (pintype "input+no_connect"))
    )
    (net (code "87") (name "unconnected-(U4-RX-Pad10)") (class "Default")
      (node (ref "U4") (pin "10") (pinfunction "RX_10") (pintype "input+no_connect"))
    )
    (net (code "88") (name "unconnected-(U4-TX-Pad9)") (class "Default")
      (node (ref "U4") (pin "9") (pinfunction "TX_9") (pintype "output"))
    )
    (net (code "89") (name "unconnected-(U4-VBACKUP-Pad4)") (class "Default")
      (node (ref "U4") (pin "4") (pinfunction "VBACKUP_4") (pintype "power_in"))
    )
  )
)
